# 5_cyber60-mx_periferals.net
KiCad netlist of a schematic drawn in Altium Designer
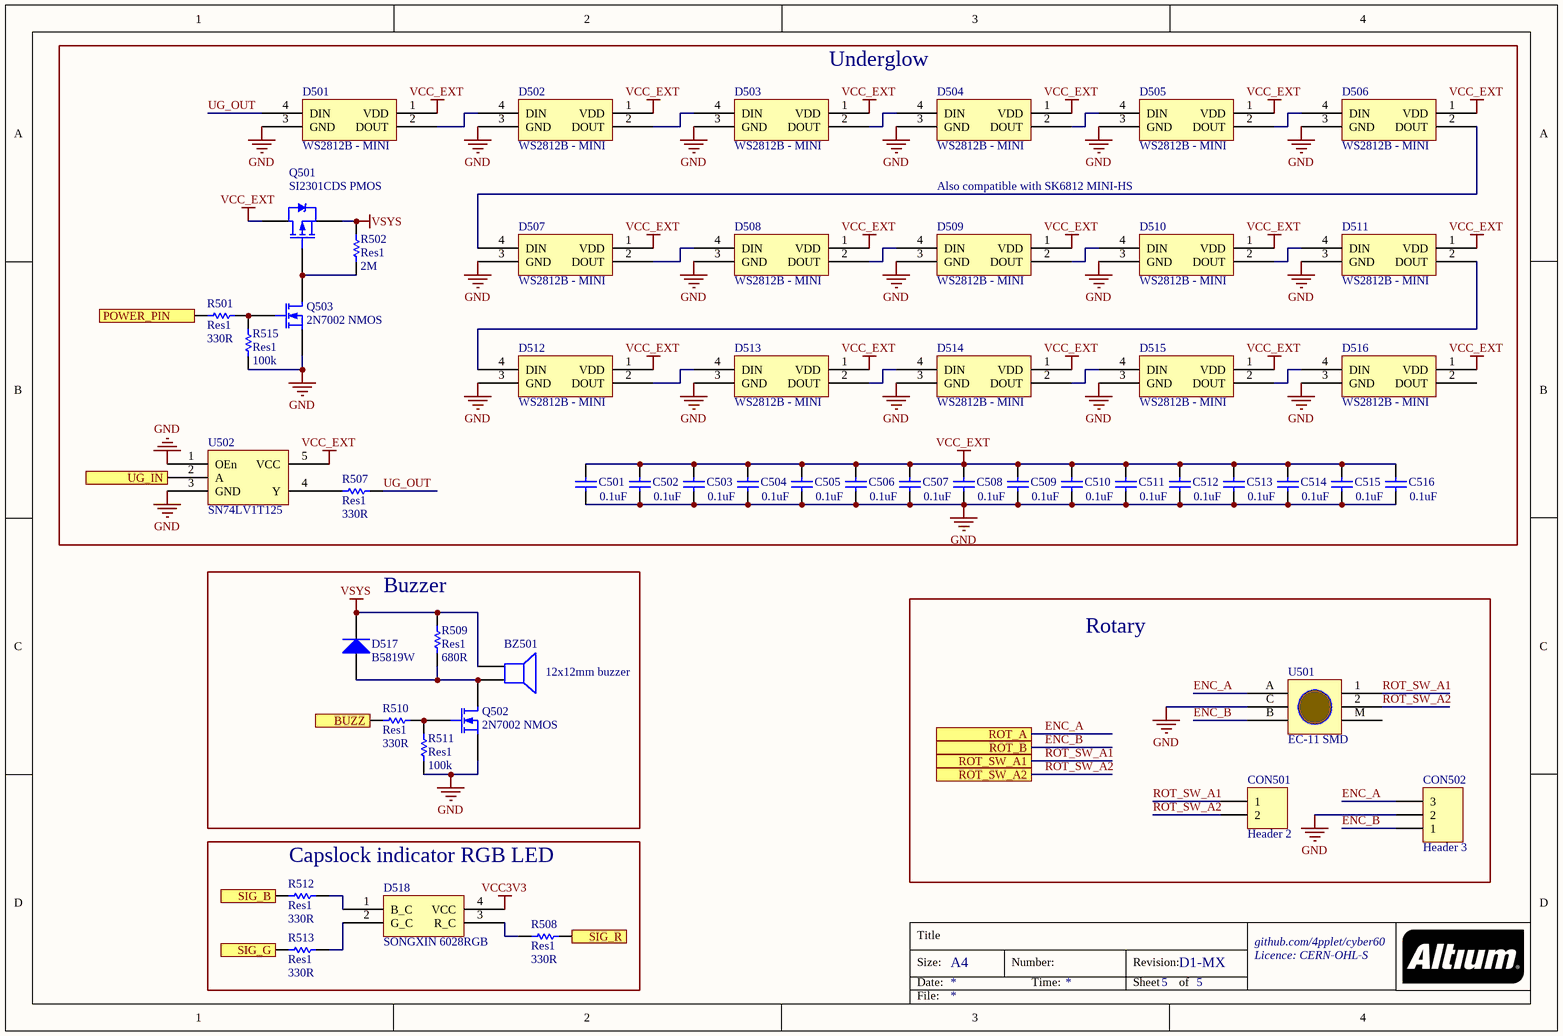
[diagram p0: 5_cyber60-mx_periferals.SchDoc]

(export (version "E")
  (design (tool "Eeschema 10.0.6"))
  (components
    (comp (ref "BZ501")
      (value "12x12mm buzzer")
      (footprint "buzzer 12x12")
      (description "Loudspeaker")
      (fields (field (name "LCSC PART #") "C409829") (field (name "MRF.PART") "YS-SBZ1230"))
      (libsource (lib "Miscellaneous Devices") (part "Speaker"))
    )
    (comp (ref "C501")
      (value "0.1uF")
      (footprint "C0603[1608]")
      (description "Capacitor")
      (fields (field (name "MFG") "KEMET") (field (name "LCSC PART #") "C14663"))
      (libsource (lib "Miscellaneous Devices") (part "Cap"))
    )
    (comp (ref "C502")
      (value "0.1uF")
      (footprint "C0603[1608]")
      (description "Capacitor")
      (fields (field (name "MFG") "KEMET") (field (name "LCSC PART #") "C14663"))
      (libsource (lib "Miscellaneous Devices") (part "Cap"))
    )
    (comp (ref "C503")
      (value "0.1uF")
      (footprint "C0603[1608]")
      (description "Capacitor")
      (fields (field (name "MFG") "KEMET") (field (name "LCSC PART #") "C14663"))
      (libsource (lib "Miscellaneous Devices") (part "Cap"))
    )
    (comp (ref "C504")
      (value "0.1uF")
      (footprint "C0603[1608]")
      (description "Capacitor")
      (fields (field (name "MFG") "KEMET") (field (name "LCSC PART #") "C14663"))
      (libsource (lib "Miscellaneous Devices") (part "Cap"))
    )
    (comp (ref "C505")
      (value "0.1uF")
      (footprint "C0603[1608]")
      (description "Capacitor")
      (fields (field (name "MFG") "KEMET") (field (name "LCSC PART #") "C14663"))
      (libsource (lib "Miscellaneous Devices") (part "Cap"))
    )
    (comp (ref "C506")
      (value "0.1uF")
      (footprint "C0603[1608]")
      (description "Capacitor")
      (fields (field (name "MFG") "KEMET") (field (name "LCSC PART #") "C14663"))
      (libsource (lib "Miscellaneous Devices") (part "Cap"))
    )
    (comp (ref "C507")
      (value "0.1uF")
      (footprint "C0603[1608]")
      (description "Capacitor")
      (fields (field (name "MFG") "KEMET") (field (name "LCSC PART #") "C14663"))
      (libsource (lib "Miscellaneous Devices") (part "Cap"))
    )
    (comp (ref "C508")
      (value "0.1uF")
      (footprint "C0603[1608]")
      (description "Capacitor")
      (fields (field (name "MFG") "KEMET") (field (name "LCSC PART #") "C14663"))
      (libsource (lib "Miscellaneous Devices") (part "Cap"))
    )
    (comp (ref "C509")
      (value "0.1uF")
      (footprint "C0603[1608]")
      (description "Capacitor")
      (fields (field (name "MFG") "KEMET") (field (name "LCSC PART #") "C14663"))
      (libsource (lib "Miscellaneous Devices") (part "Cap"))
    )
    (comp (ref "C510")
      (value "0.1uF")
      (footprint "C0603[1608]")
      (description "Capacitor")
      (fields (field (name "MFG") "KEMET") (field (name "LCSC PART #") "C14663"))
      (libsource (lib "Miscellaneous Devices") (part "Cap"))
    )
    (comp (ref "C511")
      (value "0.1uF")
      (footprint "C0603[1608]")
      (description "Capacitor")
      (fields (field (name "MFG") "KEMET") (field (name "LCSC PART #") "C14663"))
      (libsource (lib "Miscellaneous Devices") (part "Cap"))
    )
    (comp (ref "C512")
      (value "0.1uF")
      (footprint "C0603[1608]")
      (description "Capacitor")
      (fields (field (name "MFG") "KEMET") (field (name "LCSC PART #") "C14663"))
      (libsource (lib "Miscellaneous Devices") (part "Cap"))
    )
    (comp (ref "C513")
      (value "0.1uF")
      (footprint "C0603[1608]")
      (description "Capacitor")
      (fields (field (name "MFG") "KEMET") (field (name "LCSC PART #") "C14663"))
      (libsource (lib "Miscellaneous Devices") (part "Cap"))
    )
    (comp (ref "C514")
      (value "0.1uF")
      (footprint "C0603[1608]")
      (description "Capacitor")
      (fields (field (name "MFG") "KEMET") (field (name "LCSC PART #") "C14663"))
      (libsource (lib "Miscellaneous Devices") (part "Cap"))
    )
    (comp (ref "C515")
      (value "0.1uF")
      (footprint "C0603[1608]")
      (description "Capacitor")
      (fields (field (name "MFG") "KEMET") (field (name "LCSC PART #") "C14663"))
      (libsource (lib "Miscellaneous Devices") (part "Cap"))
    )
    (comp (ref "C516")
      (value "0.1uF")
      (footprint "C0603[1608]")
      (description "Capacitor")
      (fields (field (name "MFG") "KEMET") (field (name "LCSC PART #") "C14663"))
      (libsource (lib "Miscellaneous Devices") (part "Cap"))
    )
    (comp (ref "CON501")
      (value "Header 2")
      (footprint "HDR1X2")
      (description "Header, 2-Pin")
      (libsource (lib "Miscellaneous Connectors") (part "Header 2"))
    )
    (comp (ref "CON502")
      (value "Header 3")
      (footprint "HDR1X3")
      (description "Header, 3-Pin")
      (libsource (lib "Miscellaneous Connectors") (part "Header 3"))
    )
    (comp (ref "D501")
      (value "WS2812B - MINI")
      (footprint "WS2812B - 2020")
      (fields (field (name "LCSC PART #") "C965556") (field (name "MRF.PART") "WS2812C-2020"))
      (libsource (lib "Keebs") (part "WS2812B"))
    )
    (comp (ref "D502")
      (value "WS2812B - MINI")
      (footprint "WS2812B - 2020")
      (fields (field (name "LCSC PART #") "C965556") (field (name "MRF.PART") "WS2812C-2020"))
      (libsource (lib "Keebs") (part "WS2812B"))
    )
    (comp (ref "D503")
      (value "WS2812B - MINI")
      (footprint "WS2812B - 2020")
      (fields (field (name "LCSC PART #") "C965556") (field (name "MRF.PART") "WS2812C-2020"))
      (libsource (lib "Keebs") (part "WS2812B"))
    )
    (comp (ref "D504")
      (value "WS2812B - MINI")
      (footprint "WS2812B - 2020")
      (fields (field (name "LCSC PART #") "C965556") (field (name "MRF.PART") "WS2812C-2020"))
      (libsource (lib "Keebs") (part "WS2812B"))
    )
    (comp (ref "D505")
      (value "WS2812B - MINI")
      (footprint "WS2812B - 2020")
      (fields (field (name "LCSC PART #") "C965556") (field (name "MRF.PART") "WS2812C-2020"))
      (libsource (lib "Keebs") (part "WS2812B"))
    )
    (comp (ref "D506")
      (value "WS2812B - MINI")
      (footprint "WS2812B - 2020")
      (fields (field (name "LCSC PART #") "C965556") (field (name "MRF.PART") "WS2812C-2020"))
      (libsource (lib "Keebs") (part "WS2812B"))
    )
    (comp (ref "D507")
      (value "WS2812B - MINI")
      (footprint "WS2812B - 2020")
      (fields (field (name "LCSC PART #") "C965556") (field (name "MRF.PART") "WS2812C-2020"))
      (libsource (lib "Keebs") (part "WS2812B"))
    )
    (comp (ref "D508")
      (value "WS2812B - MINI")
      (footprint "WS2812B - 2020")
      (fields (field (name "LCSC PART #") "C965556") (field (name "MRF.PART") "WS2812C-2020"))
      (libsource (lib "Keebs") (part "WS2812B"))
    )
    (comp (ref "D509")
      (value "WS2812B - MINI")
      (footprint "WS2812B - 2020")
      (fields (field (name "LCSC PART #") "C965556") (field (name "MRF.PART") "WS2812C-2020"))
      (libsource (lib "Keebs") (part "WS2812B"))
    )
    (comp (ref "D510")
      (value "WS2812B - MINI")
      (footprint "WS2812B - 2020")
      (fields (field (name "LCSC PART #") "C965556") (field (name "MRF.PART") "WS2812C-2020"))
      (libsource (lib "Keebs") (part "WS2812B"))
    )
    (comp (ref "D511")
      (value "WS2812B - MINI")
      (footprint "WS2812B - 2020")
      (fields (field (name "LCSC PART #") "C965556") (field (name "MRF.PART") "WS2812C-2020"))
      (libsource (lib "Keebs") (part "WS2812B"))
    )
    (comp (ref "D512")
      (value "WS2812B - MINI")
      (footprint "WS2812B - 2020")
      (fields (field (name "LCSC PART #") "C965556") (field (name "MRF.PART") "WS2812C-2020"))
      (libsource (lib "Keebs") (part "WS2812B"))
    )
    (comp (ref "D513")
      (value "WS2812B - MINI")
      (footprint "WS2812B - 2020")
      (fields (field (name "LCSC PART #") "C965556") (field (name "MRF.PART") "WS2812C-2020"))
      (libsource (lib "Keebs") (part "WS2812B"))
    )
    (comp (ref "D514")
      (value "WS2812B - MINI")
      (footprint "WS2812B - 2020")
      (fields (field (name "LCSC PART #") "C965556") (field (name "MRF.PART") "WS2812C-2020"))
      (libsource (lib "Keebs") (part "WS2812B"))
    )
    (comp (ref "D515")
      (value "WS2812B - MINI")
      (footprint "WS2812B - 2020")
      (fields (field (name "LCSC PART #") "C965556") (field (name "MRF.PART") "WS2812C-2020"))
      (libsource (lib "Keebs") (part "WS2812B"))
    )
    (comp (ref "D516")
      (value "WS2812B - MINI")
      (footprint "WS2812B - 2020")
      (fields (field (name "LCSC PART #") "C965556") (field (name "MRF.PART") "WS2812C-2020"))
      (libsource (lib "Keebs") (part "WS2812B"))
    )
    (comp (ref "D517")
      (value "B5819W")
      (footprint "SOD-123")
      (description "Default Diode")
      (fields (field (name "LCSC PART #") "C8598"))
      (libsource (lib "Miscellaneous Devices") (part "Diode"))
    )
    (comp (ref "D518")
      (value "SONGXIN 6028RGB")
      (footprint "SONGXIN 6028RGB")
      (libsource (lib "Keebs") (part "SONGXIN 6028RGB"))
    )
    (comp (ref "Q501")
      (value "SI2301CDS PMOS")
      (footprint "SOT-23-3")
      (description "P-Channel Power MOSFET")
      (fields (field (name "MRF.PART") "SI2301CDS-T1-GE3") (field (name "LCSC PART #") "C10487"))
      (libsource (lib "Miscellaneous Devices") (part "PMOS-2"))
    )
    (comp (ref "Q502")
      (value "2N7002 NMOS")
      (footprint "SOT-23-3")
      (description "N-Channel MOSFET")
      (fields (field (name "LCSC PART #") "C8545") (field (name "MRF.PART") "2N7002"))
      (libsource (lib "Miscellaneous Devices") (part "MOSFET-N"))
    )
    (comp (ref "Q503")
      (value "2N7002 NMOS")
      (footprint "SOT-23-3")
      (description "N-Channel MOSFET")
      (fields (field (name "LCSC PART #") "C8545") (field (name "MRF.PART") "2N7002"))
      (libsource (lib "Miscellaneous Devices") (part "MOSFET-N"))
    )
    (comp (ref "R501")
      (value "Res1")
      (footprint "R0603[1608]")
      (description "Resistor")
      (fields
        (field (name "ALTIUM_VALUE") "330R")
        (field (name "LCSC PART #") "C23138")
        (field (name "MRF.PART") "0603WAF3300T5E")
      )
      (libsource (lib "Miscellaneous Devices") (part "Res1"))
    )
    (comp (ref "R502")
      (value "Res1")
      (footprint "R0603[1608]")
      (description "Resistor")
      (fields
        (field (name "ALTIUM_VALUE") "2M")
        (field (name "MRF.PART") "0603WAF2004T5E")
        (field (name "LCSC PART #") "C22976")
      )
      (libsource (lib "Miscellaneous Devices") (part "Res1"))
    )
    (comp (ref "R507")
      (value "Res1")
      (footprint "R0603[1608]")
      (description "Resistor")
      (fields
        (field (name "ALTIUM_VALUE") "330R")
        (field (name "LCSC PART #") "C23138")
        (field (name "MRF.PART") "0603WAF3300T5E")
      )
      (libsource (lib "Miscellaneous Devices") (part "Res1"))
    )
    (comp (ref "R508")
      (value "Res1")
      (footprint "R0603[1608]")
      (description "Resistor")
      (fields
        (field (name "ALTIUM_VALUE") "330R")
        (field (name "LCSC PART #") "C23138")
        (field (name "MRF.PART") "0603WAF3300T5E")
      )
      (libsource (lib "Miscellaneous Devices") (part "Res1"))
    )
    (comp (ref "R509")
      (value "Res1")
      (footprint "R0603[1608]")
      (description "Resistor")
      (fields
        (field (name "ALTIUM_VALUE") "680R")
        (field (name "MRF.PART") "0603WAF6800T5E")
        (field (name "LCSC PART #") "C23228")
      )
      (libsource (lib "Miscellaneous Devices") (part "Res1"))
    )
    (comp (ref "R510")
      (value "Res1")
      (footprint "R0603[1608]")
      (description "Resistor")
      (fields
        (field (name "ALTIUM_VALUE") "330R")
        (field (name "LCSC PART #") "C23138")
        (field (name "MRF.PART") "0603WAF3300T5E")
      )
      (libsource (lib "Miscellaneous Devices") (part "Res1"))
    )
    (comp (ref "R511")
      (value "Res1")
      (footprint "R0603[1608]")
      (description "Resistor")
      (fields
        (field (name "ALTIUM_VALUE") "100k")
        (field (name "MRF.PART") "0603WAF1003T5E")
        (field (name "LCSC PART #") "C25803")
      )
      (libsource (lib "Miscellaneous Devices") (part "Res1"))
    )
    (comp (ref "R512")
      (value "Res1")
      (footprint "R0603[1608]")
      (description "Resistor")
      (fields
        (field (name "ALTIUM_VALUE") "330R")
        (field (name "LCSC PART #") "C23138")
        (field (name "MRF.PART") "0603WAF3300T5E")
      )
      (libsource (lib "Miscellaneous Devices") (part "Res1"))
    )
    (comp (ref "R513")
      (value "Res1")
      (footprint "R0603[1608]")
      (description "Resistor")
      (fields
        (field (name "ALTIUM_VALUE") "330R")
        (field (name "LCSC PART #") "C23138")
        (field (name "MRF.PART") "0603WAF3300T5E")
      )
      (libsource (lib "Miscellaneous Devices") (part "Res1"))
    )
    (comp (ref "R515")
      (value "Res1")
      (footprint "R0603[1608]")
      (description "Resistor")
      (fields
        (field (name "ALTIUM_VALUE") "100k")
        (field (name "MRF.PART") "0603WAF1003T5E")
        (field (name "LCSC PART #") "C25803")
      )
      (libsource (lib "Miscellaneous Devices") (part "Res1"))
    )
    (comp (ref "U501") (value "EC-11 SMD") (footprint "EC11-SMD") (libsource (lib "Keebs") (part "EC-11")))
    (comp (ref "U502")
      (value "SN74LV1T125")
      (footprint "SOT-23-5")
      (description "SN74LV1T125 or SN74LV1T34. Connect OE to GND")
      (fields (field (name "LCSC PART #") "C473338") (field (name "MRF.PART") "SN74LV1T125DBVR"))
      (libsource (lib "Keebs") (part "SN74LV1T125"))
    )
  )
  (nets
    (net (code "1") (name "/BUZZ") (class "Default")
      (node (ref "R510") (pin "2") (pinfunction "2_2") (pintype "passive"))
    )
    (net (code "2") (name "/ENC_A") (class "Default")
      (node (ref "CON502") (pin "3") (pinfunction "3_3") (pintype "passive"))
      (node (ref "U501") (pin "A") (pinfunction "B_A") (pintype "passive"))
    )
    (net (code "3") (name "/ENC_B") (class "Default")
      (node (ref "CON502") (pin "1") (pinfunction "1_1") (pintype "passive"))
      (node (ref "U501") (pin "B") (pinfunction "B_B") (pintype "passive"))
    )
    (net (code "4") (name "/POWER_PIN") (class "Default")
      (node (ref "R501") (pin "1") (pinfunction "1_1") (pintype "passive"))
    )
    (net (code "5") (name "/ROT_SW_A1") (class "Default")
      (node (ref "CON501") (pin "1") (pinfunction "1_1") (pintype "passive"))
      (node (ref "U501") (pin "1") (pinfunction "1_1") (pintype "passive"))
    )
    (net (code "6") (name "/ROT_SW_A2") (class "Default")
      (node (ref "CON501") (pin "2") (pinfunction "2_2") (pintype "passive"))
      (node (ref "U501") (pin "2") (pinfunction "2_2") (pintype "passive"))
    )
    (net (code "7") (name "/SIG_B") (class "Default")
      (node (ref "R512") (pin "2") (pinfunction "2_2") (pintype "passive"))
    )
    (net (code "8") (name "/SIG_G") (class "Default")
      (node (ref "R513") (pin "2") (pinfunction "2_2") (pintype "passive"))
    )
    (net (code "9") (name "/SIG_R") (class "Default")
      (node (ref "R508") (pin "1") (pinfunction "1_1") (pintype "passive"))
    )
    (net (code "10") (name "/UG_IN") (class "Default")
      (node (ref "U502") (pin "2") (pinfunction "A_2") (pintype "passive"))
    )
    (net (code "11") (name "/UG_OUT") (class "Default")
      (node (ref "D501") (pin "4") (pinfunction "DIN_4") (pintype "passive"))
      (node (ref "R507") (pin "1") (pinfunction "1_1") (pintype "passive"))
    )
    (net (code "12") (name "GND") (class "Default")
      (node (ref "C501") (pin "1") (pinfunction "1_1") (pintype "passive"))
      (node (ref "C502") (pin "1") (pinfunction "1_1") (pintype "passive"))
      (node (ref "C503") (pin "1") (pinfunction "1_1") (pintype "passive"))
      (node (ref "C504") (pin "1") (pinfunction "1_1") (pintype "passive"))
      (node (ref "C505") (pin "1") (pinfunction "1_1") (pintype "passive"))
      (node (ref "C506") (pin "1") (pinfunction "1_1") (pintype "passive"))
      (node (ref "C507") (pin "1") (pinfunction "1_1") (pintype "passive"))
      (node (ref "C508") (pin "1") (pinfunction "1_1") (pintype "passive"))
      (node (ref "C509") (pin "1") (pinfunction "1_1") (pintype "passive"))
      (node (ref "C510") (pin "1") (pinfunction "1_1") (pintype "passive"))
      (node (ref "C511") (pin "1") (pinfunction "1_1") (pintype "passive"))
      (node (ref "C512") (pin "1") (pinfunction "1_1") (pintype "passive"))
      (node (ref "C513") (pin "1") (pinfunction "1_1") (pintype "passive"))
      (node (ref "C514") (pin "1") (pinfunction "1_1") (pintype "passive"))
      (node (ref "C515") (pin "1") (pinfunction "1_1") (pintype "passive"))
      (node (ref "C516") (pin "1") (pinfunction "1_1") (pintype "passive"))
      (node (ref "CON502") (pin "2") (pinfunction "2_2") (pintype "passive"))
      (node (ref "D501") (pin "3") (pinfunction "GND_3") (pintype "passive"))
      (node (ref "D502") (pin "3") (pinfunction "GND_3") (pintype "passive"))
      (node (ref "D503") (pin "3") (pinfunction "GND_3") (pintype "passive"))
      (node (ref "D504") (pin "3") (pinfunction "GND_3") (pintype "passive"))
      (node (ref "D505") (pin "3") (pinfunction "GND_3") (pintype "passive"))
      (node (ref "D506") (pin "3") (pinfunction "GND_3") (pintype "passive"))
      (node (ref "D507") (pin "3") (pinfunction "GND_3") (pintype "passive"))
      (node (ref "D508") (pin "3") (pinfunction "GND_3") (pintype "passive"))
      (node (ref "D509") (pin "3") (pinfunction "GND_3") (pintype "passive"))
      (node (ref "D510") (pin "3") (pinfunction "GND_3") (pintype "passive"))
      (node (ref "D511") (pin "3") (pinfunction "GND_3") (pintype "passive"))
      (node (ref "D512") (pin "3") (pinfunction "GND_3") (pintype "passive"))
      (node (ref "D513") (pin "3") (pinfunction "GND_3") (pintype "passive"))
      (node (ref "D514") (pin "3") (pinfunction "GND_3") (pintype "passive"))
      (node (ref "D515") (pin "3") (pinfunction "GND_3") (pintype "passive"))
      (node (ref "D516") (pin "3") (pinfunction "GND_3") (pintype "passive"))
      (node (ref "Q502") (pin "2") (pinfunction "S_2") (pintype "passive"))
      (node (ref "Q503") (pin "2") (pinfunction "S_2") (pintype "passive"))
      (node (ref "R511") (pin "2") (pinfunction "2_2") (pintype "passive"))
      (node (ref "R515") (pin "2") (pinfunction "2_2") (pintype "passive"))
      (node (ref "U501") (pin "C") (pinfunction "C_C") (pintype "passive"))
      (node (ref "U502") (pin "1") (pinfunction "OEn_1") (pintype "passive"))
      (node (ref "U502") (pin "3") (pinfunction "GND_3") (pintype "passive"))
    )
    (net (code "13") (name "Net-(D501-DOUT)") (class "Default")
      (node (ref "D501") (pin "2") (pinfunction "DOUT_2") (pintype "passive"))
      (node (ref "D502") (pin "4") (pinfunction "DIN_4") (pintype "passive"))
    )
    (net (code "14") (name "Net-(D502-DOUT)") (class "Default")
      (node (ref "D502") (pin "2") (pinfunction "DOUT_2") (pintype "passive"))
      (node (ref "D503") (pin "4") (pinfunction "DIN_4") (pintype "passive"))
    )
    (net (code "15") (name "Net-(D503-DOUT)") (class "Default")
      (node (ref "D503") (pin "2") (pinfunction "DOUT_2") (pintype "passive"))
      (node (ref "D504") (pin "4") (pinfunction "DIN_4") (pintype "passive"))
    )
    (net (code "16") (name "Net-(D504-DOUT)") (class "Default")
      (node (ref "D504") (pin "2") (pinfunction "DOUT_2") (pintype "passive"))
      (node (ref "D505") (pin "4") (pinfunction "DIN_4") (pintype "passive"))
    )
    (net (code "17") (name "Net-(D505-DOUT)") (class "Default")
      (node (ref "D505") (pin "2") (pinfunction "DOUT_2") (pintype "passive"))
      (node (ref "D506") (pin "4") (pinfunction "DIN_4") (pintype "passive"))
    )
    (net (code "18") (name "Net-(D506-DOUT)") (class "Default")
      (node (ref "D506") (pin "2") (pinfunction "DOUT_2") (pintype "passive"))
      (node (ref "D507") (pin "4") (pinfunction "DIN_4") (pintype "passive"))
    )
    (net (code "19") (name "Net-(D507-DOUT)") (class "Default")
      (node (ref "D507") (pin "2") (pinfunction "DOUT_2") (pintype "passive"))
      (node (ref "D508") (pin "4") (pinfunction "DIN_4") (pintype "passive"))
    )
    (net (code "20") (name "Net-(D508-DOUT)") (class "Default")
      (node (ref "D508") (pin "2") (pinfunction "DOUT_2") (pintype "passive"))
      (node (ref "D509") (pin "4") (pinfunction "DIN_4") (pintype "passive"))
    )
    (net (code "21") (name "Net-(D509-DOUT)") (class "Default")
      (node (ref "D509") (pin "2") (pinfunction "DOUT_2") (pintype "passive"))
      (node (ref "D510") (pin "4") (pinfunction "DIN_4") (pintype "passive"))
    )
    (net (code "22") (name "Net-(D510-DOUT)") (class "Default")
      (node (ref "D510") (pin "2") (pinfunction "DOUT_2") (pintype "passive"))
      (node (ref "D511") (pin "4") (pinfunction "DIN_4") (pintype "passive"))
    )
    (net (code "23") (name "Net-(D511-DOUT)") (class "Default")
      (node (ref "D511") (pin "2") (pinfunction "DOUT_2") (pintype "passive"))
      (node (ref "D512") (pin "4") (pinfunction "DIN_4") (pintype "passive"))
    )
    (net (code "24") (name "Net-(D512-DOUT)") (class "Default")
      (node (ref "D512") (pin "2") (pinfunction "DOUT_2") (pintype "passive"))
      (node (ref "D513") (pin "4") (pinfunction "DIN_4") (pintype "passive"))
    )
    (net (code "25") (name "Net-(D513-DOUT)") (class "Default")
      (node (ref "D513") (pin "2") (pinfunction "DOUT_2") (pintype "passive"))
      (node (ref "D514") (pin "4") (pinfunction "DIN_4") (pintype "passive"))
    )
    (net (code "26") (name "Net-(D514-DOUT)") (class "Default")
      (node (ref "D514") (pin "2") (pinfunction "DOUT_2") (pintype "passive"))
      (node (ref "D515") (pin "4") (pinfunction "DIN_4") (pintype "passive"))
    )
    (net (code "27") (name "Net-(D515-DOUT)") (class "Default")
      (node (ref "D515") (pin "2") (pinfunction "DOUT_2") (pintype "passive"))
      (node (ref "D516") (pin "4") (pinfunction "DIN_4") (pintype "passive"))
    )
    (net (code "28") (name "Net-(D517-A)") (class "Default")
      (node (ref "BZ501") (pin "2") (pinfunction "2_2") (pintype "passive"))
      (node (ref "D517") (pin "1") (pinfunction "A_1") (pintype "passive"))
      (node (ref "Q502") (pin "3") (pinfunction "D_3") (pintype "passive"))
      (node (ref "R509") (pin "2") (pinfunction "2_2") (pintype "passive"))
    )
    (net (code "29") (name "Net-(D518-B_C)") (class "Default")
      (node (ref "D518") (pin "1") (pinfunction "B_C_1") (pintype "passive"))
      (node (ref "R512") (pin "1") (pinfunction "1_1") (pintype "passive"))
    )
    (net (code "30") (name "Net-(D518-G_C)") (class "Default")
      (node (ref "D518") (pin "2") (pinfunction "G_C_2") (pintype "passive"))
      (node (ref "R513") (pin "1") (pinfunction "1_1") (pintype "passive"))
    )
    (net (code "31") (name "Net-(D518-R_C)") (class "Default")
      (node (ref "D518") (pin "3") (pinfunction "R_C_3") (pintype "passive"))
      (node (ref "R508") (pin "2") (pinfunction "2_2") (pintype "passive"))
    )
    (net (code "32") (name "Net-(Q501-G)") (class "Default")
      (node (ref "Q501") (pin "1") (pinfunction "G_1") (pintype "passive"))
      (node (ref "Q503") (pin "3") (pinfunction "D_3") (pintype "passive"))
      (node (ref "R502") (pin "1") (pinfunction "1_1") (pintype "passive"))
    )
    (net (code "33") (name "Net-(Q502-G)") (class "Default")
      (node (ref "Q502") (pin "1") (pinfunction "G_1") (pintype "passive"))
      (node (ref "R510") (pin "1") (pinfunction "1_1") (pintype "passive"))
      (node (ref "R511") (pin "1") (pinfunction "1_1") (pintype "passive"))
    )
    (net (code "34") (name "Net-(Q503-G)") (class "Default")
      (node (ref "Q503") (pin "1") (pinfunction "G_1") (pintype "passive"))
      (node (ref "R501") (pin "2") (pinfunction "2_2") (pintype "passive"))
      (node (ref "R515") (pin "1") (pinfunction "1_1") (pintype "passive"))
    )
    (net (code "35") (name "Net-(U502-Y)") (class "Default")
      (node (ref "R507") (pin "2") (pinfunction "2_2") (pintype "passive"))
      (node (ref "U502") (pin "4") (pinfunction "Y_4") (pintype "passive"))
    )
    (net (code "36") (name "VCC3V3") (class "Default")
      (node (ref "D518") (pin "4") (pinfunction "VCC_4") (pintype "passive"))
    )
    (net (code "37") (name "VCC_EXT") (class "Default")
      (node (ref "C501") (pin "2") (pinfunction "2_2") (pintype "passive"))
      (node (ref "C502") (pin "2") (pinfunction "2_2") (pintype "passive"))
      (node (ref "C503") (pin "2") (pinfunction "2_2") (pintype "passive"))
      (node (ref "C504") (pin "2") (pinfunction "2_2") (pintype "passive"))
      (node (ref "C505") (pin "2") (pinfunction "2_2") (pintype "passive"))
      (node (ref "C506") (pin "2") (pinfunction "2_2") (pintype "passive"))
      (node (ref "C507") (pin "2") (pinfunction "2_2") (pintype "passive"))
      (node (ref "C508") (pin "2") (pinfunction "2_2") (pintype "passive"))
      (node (ref "C509") (pin "2") (pinfunction "2_2") (pintype "passive"))
      (node (ref "C510") (pin "2") (pinfunction "2_2") (pintype "passive"))
      (node (ref "C511") (pin "2") (pinfunction "2_2") (pintype "passive"))
      (node (ref "C512") (pin "2") (pinfunction "2_2") (pintype "passive"))
      (node (ref "C513") (pin "2") (pinfunction "2_2") (pintype "passive"))
      (node (ref "C514") (pin "2") (pinfunction "2_2") (pintype "passive"))
      (node (ref "C515") (pin "2") (pinfunction "2_2") (pintype "passive"))
      (node (ref "C516") (pin "2") (pinfunction "2_2") (pintype "passive"))
      (node (ref "D501") (pin "1") (pinfunction "VDD_1") (pintype "passive"))
      (node (ref "D502") (pin "1") (pinfunction "VDD_1") (pintype "passive"))
      (node (ref "D503") (pin "1") (pinfunction "VDD_1") (pintype "passive"))
      (node (ref "D504") (pin "1") (pinfunction "VDD_1") (pintype "passive"))
      (node (ref "D505") (pin "1") (pinfunction "VDD_1") (pintype "passive"))
      (node (ref "D506") (pin "1") (pinfunction "VDD_1") (pintype "passive"))
      (node (ref "D507") (pin "1") (pinfunction "VDD_1") (pintype "passive"))
      (node (ref "D508") (pin "1") (pinfunction "VDD_1") (pintype "passive"))
      (node (ref "D509") (pin "1") (pinfunction "VDD_1") (pintype "passive"))
      (node (ref "D510") (pin "1") (pinfunction "VDD_1") (pintype "passive"))
      (node (ref "D511") (pin "1") (pinfunction "VDD_1") (pintype "passive"))
      (node (ref "D512") (pin "1") (pinfunction "VDD_1") (pintype "passive"))
      (node (ref "D513") (pin "1") (pinfunction "VDD_1") (pintype "passive"))
      (node (ref "D514") (pin "1") (pinfunction "VDD_1") (pintype "passive"))
      (node (ref "D515") (pin "1") (pinfunction "VDD_1") (pintype "passive"))
      (node (ref "D516") (pin "1") (pinfunction "VDD_1") (pintype "passive"))
      (node (ref "Q501") (pin "3") (pinfunction "D_3") (pintype "passive"))
      (node (ref "U502") (pin "5") (pinfunction "VCC_5") (pintype "passive"))
    )
    (net (code "38") (name "VSYS") (class "Default")
      (node (ref "BZ501") (pin "1") (pinfunction "1_1") (pintype "passive"))
      (node (ref "D517") (pin "2") (pinfunction "K_2") (pintype "passive"))
      (node (ref "Q501") (pin "2") (pinfunction "S_2") (pintype "passive"))
      (node (ref "R502") (pin "2") (pinfunction "2_2") (pintype "passive"))
      (node (ref "R509") (pin "1") (pinfunction "1_1") (pintype "passive"))
    )
    (net (code "39") (name "unconnected-(D516-DOUT-Pad2)") (class "Default")
      (node (ref "D516") (pin "2") (pinfunction "DOUT_2") (pintype "passive"))
    )
    (net (code "40") (name "unconnected-(U501-PadM)") (class "Default")
      (node (ref "U501") (pin "M") (pinfunction "M_M") (pintype "passive"))
    )
  )
)
